# MCU.net
KiCad netlist of a schematic drawn in Altium Designer
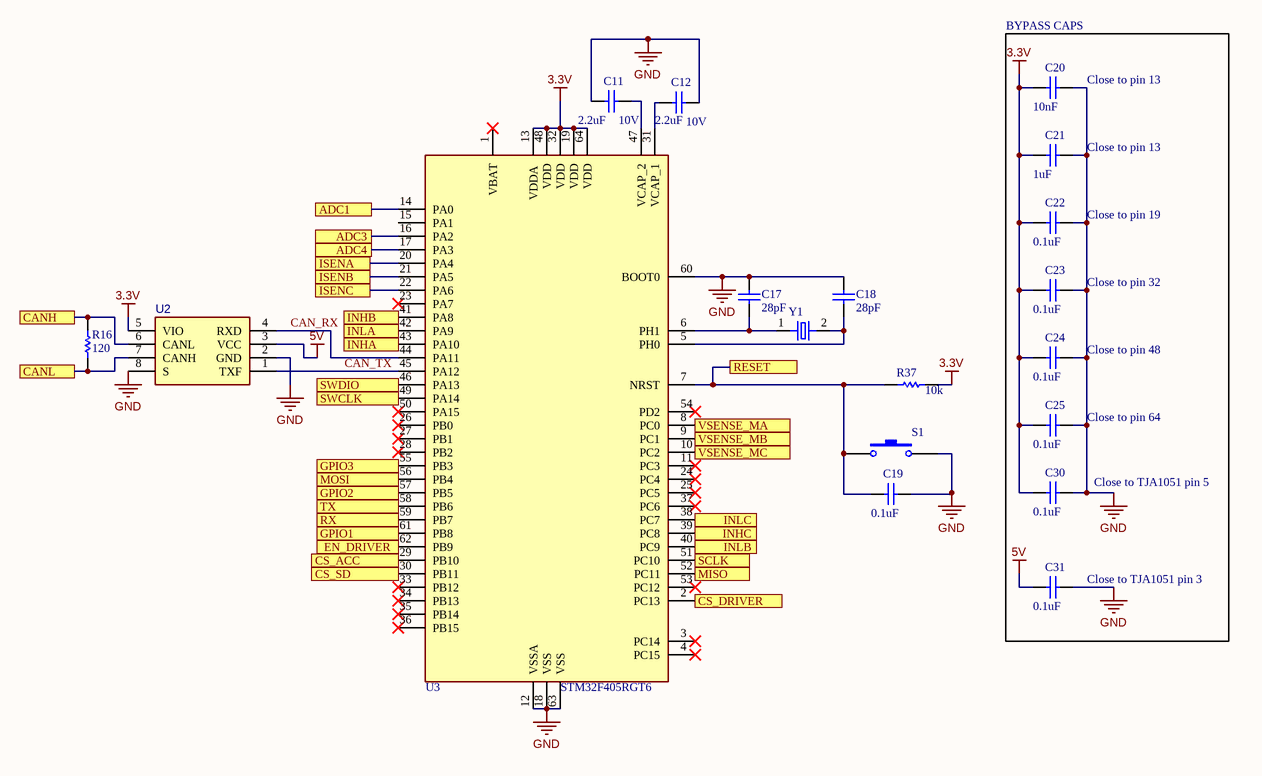
[diagram p0: MCU.SchDoc]

(export (version "E")
  (design (tool "Eeschema 10.0.6"))
  (components
    (comp (ref "C11")
      (value "10V")
      (footprint "0805 - Capacitor")
      (description "Nonpolarized Capacitor")
      (fields (field (name "ALTIUM_VALUE") "2.2uF"))
      (libsource (lib "General") (part "Capacitor - Nonpolarized"))
    )
    (comp (ref "C12")
      (value "10V")
      (footprint "0805 - Capacitor")
      (description "Nonpolarized Capacitor")
      (fields (field (name "ALTIUM_VALUE") "2.2uF"))
      (libsource (lib "General") (part "Capacitor - Nonpolarized"))
    )
    (comp (ref "C17")
      (value "28pF")
      (footprint "0805 - Capacitor")
      (description "CL21B104KCFNNNE, MULTILAYER CERAMIC CAPACITORS MLCC - SMD/SMT 100NF 100V 0805 ROHS")
      (fields (field (name "Comment") "100V"))
      (libsource (lib "General") (part "Capacitor - Nonpolarized"))
    )
    (comp (ref "C18")
      (value "28pF")
      (footprint "0805 - Capacitor")
      (description "CL21B104KCFNNNE, MULTILAYER CERAMIC CAPACITORS MLCC - SMD/SMT 100NF 100V 0805 ROHS")
      (fields (field (name "Comment") "100V"))
      (libsource (lib "General") (part "Capacitor - Nonpolarized"))
    )
    (comp (ref "C19")
      (value "0.1uF")
      (footprint "0805 - Capacitor")
      (description "CL21B104KCFNNNE, MULTILAYER CERAMIC CAPACITORS MLCC - SMD/SMT 100NF 100V 0805 ROHS")
      (fields (field (name "Comment") "100V"))
      (libsource (lib "General") (part "Capacitor - Nonpolarized"))
    )
    (comp (ref "C20")
      (value "10nF")
      (footprint "0805 - Capacitor")
      (description "C0805C103K8RAC7800. 10000pF ±10% 10V Ceramic Capacitor X7R 0805 (2012 Metric)")
      (fields (field (name "Comment") "10V"))
      (libsource (lib "General") (part "Capacitor - Nonpolarized"))
    )
    (comp (ref "C21")
      (value "1uF")
      (footprint "0805 - Capacitor")
      (description "TDK C2012X7S2A105KT000N, 1UF ±10% 100V X7S 0805 MULTILAYER CERAMIC CAPACITORS MLCC - SMD/SMT ROHS")
      (fields (field (name "Comment") "100V"))
      (libsource (lib "General") (part "Capacitor - Nonpolarized"))
    )
    (comp (ref "C22")
      (value "0.1uF")
      (footprint "0805 - Capacitor")
      (description "CL21B104KCFNNNE, MULTILAYER CERAMIC CAPACITORS MLCC - SMD/SMT 100NF 100V 0805 ROHS")
      (fields (field (name "Comment") "100V"))
      (libsource (lib "General") (part "Capacitor - Nonpolarized"))
    )
    (comp (ref "C23")
      (value "0.1uF")
      (footprint "0805 - Capacitor")
      (description "CL21B104KCFNNNE, MULTILAYER CERAMIC CAPACITORS MLCC - SMD/SMT 100NF 100V 0805 ROHS")
      (fields (field (name "Comment") "100V"))
      (libsource (lib "General") (part "Capacitor - Nonpolarized"))
    )
    (comp (ref "C24")
      (value "0.1uF")
      (footprint "0805 - Capacitor")
      (description "CL21B104KCFNNNE, MULTILAYER CERAMIC CAPACITORS MLCC - SMD/SMT 100NF 100V 0805 ROHS")
      (fields (field (name "Comment") "100V"))
      (libsource (lib "General") (part "Capacitor - Nonpolarized"))
    )
    (comp (ref "C25")
      (value "0.1uF")
      (footprint "0805 - Capacitor")
      (description "CL21B104KCFNNNE, MULTILAYER CERAMIC CAPACITORS MLCC - SMD/SMT 100NF 100V 0805 ROHS")
      (fields (field (name "Comment") "100V"))
      (libsource (lib "General") (part "Capacitor - Nonpolarized"))
    )
    (comp (ref "C30")
      (value "0.1uF")
      (footprint "0805 - Capacitor")
      (description "CL21B104KCFNNNE, MULTILAYER CERAMIC CAPACITORS MLCC - SMD/SMT 100NF 100V 0805 ROHS")
      (fields (field (name "Comment") "100V"))
      (libsource (lib "General") (part "Capacitor - Nonpolarized"))
    )
    (comp (ref "C31")
      (value "0.1uF")
      (footprint "0805 - Capacitor")
      (description "CL21B104KCFNNNE, MULTILAYER CERAMIC CAPACITORS MLCC - SMD/SMT 100NF 100V 0805 ROHS")
      (fields (field (name "Comment") "100V"))
      (libsource (lib "General") (part "Capacitor - Nonpolarized"))
    )
    (comp (ref "R16")
      (value "120")
      (footprint "0603 - Resistor")
      (description "Resistor")
      (fields (field (name "Comment") "500m"))
      (libsource (lib "General") (part "Resistor"))
    )
    (comp (ref "R37")
      (value "10k")
      (footprint "0603 - Resistor")
      (description "Resistor")
      (libsource (lib "General") (part "Resistor"))
    )
    (comp (ref "S1")
      (value "Switch - Push Button")
      (footprint "6x6mm Switch")
      (description "Push Button Switch")
      (libsource (lib "General") (part "Switch - Push Button"))
    )
    (comp (ref "U2")
      (value "~")
      (footprint "TJA1051T/3,118")
      (description "Integrated Circuit")
      (fields
        (field (name "MANUFACTURER_PART_NUMBER") "TJA1051T/3,118")
        (field (name "MOUSER PART NUMBER") "771-TJA1051T3118")
      )
      (libsource (lib "GeneralComponents") (part "TJA1051T_3,118"))
    )
    (comp (ref "U3")
      (value "STM32F405RGT6")
      (footprint "STM32F405RG")
      (description "ST 64-pin Micro")
      (fields (field (name "MANUFACTURER PART NUMBER") "STM32F405RG") (field (name "MANUFACTURER") "ST"))
      (libsource (lib "GeneralComponents") (part "STM32F405RGT6"))
    )
    (comp (ref "Y1")
      (value "ABM3-16.000MHZ-B2-T")
      (footprint "ABM3-16.000MHZ-B2-T")
      (description "16MHz Â±20ppm Crystal 18pF 40 Ohms 2-SMD, No Lead")
      (fields (field (name "DIGI-KEY_PART_NUMBER") "535-9103-1-ND") (field (name "MF") "Abracon"))
      (libsource (lib "MC") (part "ABM3-16.000MHZ-B2-T"))
    )
  )
  (nets
    (net (code "1") (name "/ADC1") (class "Default")
      (node (ref "U3") (pin "14") (pinfunction "PA0_14") (pintype "passive"))
    )
    (net (code "2") (name "/ADC3") (class "Default")
      (node (ref "U3") (pin "16") (pinfunction "PA2_16") (pintype "passive"))
    )
    (net (code "3") (name "/ADC4") (class "Default")
      (node (ref "U3") (pin "17") (pinfunction "PA3_17") (pintype "passive"))
    )
    (net (code "4") (name "/CANH") (class "Default")
      (node (ref "R16") (pin "1") (pinfunction "1_1") (pintype "passive"))
      (node (ref "U2") (pin "6") (pinfunction "CANL_6") (pintype "passive"))
    )
    (net (code "5") (name "/CANL") (class "Default")
      (node (ref "R16") (pin "2") (pinfunction "2_2") (pintype "passive"))
      (node (ref "U2") (pin "7") (pinfunction "CANH_7") (pintype "passive"))
    )
    (net (code "6") (name "/CAN_RX") (class "Default")
      (node (ref "U2") (pin "4") (pinfunction "RXD_4") (pintype "passive"))
      (node (ref "U3") (pin "44") (pinfunction "PA11_44") (pintype "passive"))
    )
    (net (code "7") (name "/CAN_TX") (class "Default")
      (node (ref "U2") (pin "1") (pinfunction "TXF_1") (pintype "passive"))
      (node (ref "U3") (pin "45") (pinfunction "PA12_45") (pintype "passive"))
    )
    (net (code "8") (name "/CS_ACC") (class "Default")
      (node (ref "U3") (pin "29") (pinfunction "PB10_29") (pintype "passive"))
    )
    (net (code "9") (name "/CS_DRIVER") (class "Default")
      (node (ref "U3") (pin "2") (pinfunction "PC13_2") (pintype "passive"))
    )
    (net (code "10") (name "/CS_SD") (class "Default")
      (node (ref "U3") (pin "30") (pinfunction "PB11_30") (pintype "passive"))
    )
    (net (code "11") (name "/EN_DRIVER") (class "Default")
      (node (ref "U3") (pin "62") (pinfunction "PB9_62") (pintype "passive"))
    )
    (net (code "12") (name "/GPIO1") (class "Default")
      (node (ref "U3") (pin "61") (pinfunction "PB8_61") (pintype "passive"))
    )
    (net (code "13") (name "/GPIO2") (class "Default")
      (node (ref "U3") (pin "57") (pinfunction "PB5_57") (pintype "passive"))
    )
    (net (code "14") (name "/GPIO3") (class "Default")
      (node (ref "U3") (pin "55") (pinfunction "PB3_55") (pintype "passive"))
    )
    (net (code "15") (name "/INHA") (class "Default")
      (node (ref "U3") (pin "43") (pinfunction "PA10_43") (pintype "passive"))
    )
    (net (code "16") (name "/INHB") (class "Default")
      (node (ref "U3") (pin "41") (pinfunction "PA8_41") (pintype "passive"))
    )
    (net (code "17") (name "/INHC") (class "Default")
      (node (ref "U3") (pin "39") (pinfunction "PC8_39") (pintype "passive"))
    )
    (net (code "18") (name "/INLA") (class "Default")
      (node (ref "U3") (pin "42") (pinfunction "PA9_42") (pintype "passive"))
    )
    (net (code "19") (name "/INLB") (class "Default")
      (node (ref "U3") (pin "40") (pinfunction "PC9_40") (pintype "passive"))
    )
    (net (code "20") (name "/INLC") (class "Default")
      (node (ref "U3") (pin "38") (pinfunction "PC7_38") (pintype "passive"))
    )
    (net (code "21") (name "/ISENA") (class "Default")
      (node (ref "U3") (pin "20") (pinfunction "PA4_20") (pintype "passive"))
    )
    (net (code "22") (name "/ISENB") (class "Default")
      (node (ref "U3") (pin "21") (pinfunction "PA5_21") (pintype "passive"))
    )
    (net (code "23") (name "/ISENC") (class "Default")
      (node (ref "U3") (pin "22") (pinfunction "PA6_22") (pintype "passive"))
    )
    (net (code "24") (name "/MISO") (class "Default")
      (node (ref "U3") (pin "52") (pinfunction "PC11_52") (pintype "passive"))
    )
    (net (code "25") (name "/MOSI") (class "Default")
      (node (ref "U3") (pin "56") (pinfunction "PB4_56") (pintype "passive"))
    )
    (net (code "26") (name "/RESET") (class "Default")
      (node (ref "C19") (pin "1") (pinfunction "1_1") (pintype "passive"))
      (node (ref "R37") (pin "2") (pinfunction "2_2") (pintype "passive"))
      (node (ref "S1") (pin "1") (pinfunction "1_1") (pintype "passive"))
      (node (ref "U3") (pin "7") (pinfunction "NRST_7") (pintype "passive"))
    )
    (net (code "27") (name "/RX") (class "Default")
      (node (ref "U3") (pin "59") (pinfunction "PB7_59") (pintype "passive"))
    )
    (net (code "28") (name "/SCLK") (class "Default")
      (node (ref "U3") (pin "51") (pinfunction "PC10_51") (pintype "passive"))
    )
    (net (code "29") (name "/SWCLK") (class "Default")
      (node (ref "U3") (pin "49") (pinfunction "PA14_49") (pintype "passive"))
    )
    (net (code "30") (name "/SWDIO") (class "Default")
      (node (ref "U3") (pin "46") (pinfunction "PA13_46") (pintype "passive"))
    )
    (net (code "31") (name "/TX") (class "Default")
      (node (ref "U3") (pin "58") (pinfunction "PB6_58") (pintype "passive"))
    )
    (net (code "32") (name "/VSENSE_MA") (class "Default")
      (node (ref "U3") (pin "8") (pinfunction "PC0_8") (pintype "passive"))
    )
    (net (code "33") (name "/VSENSE_MB") (class "Default")
      (node (ref "U3") (pin "9") (pinfunction "PC1_9") (pintype "passive"))
    )
    (net (code "34") (name "/VSENSE_MC") (class "Default")
      (node (ref "U3") (pin "10") (pinfunction "PC2_10") (pintype "passive"))
    )
    (net (code "35") (name "3.3V") (class "Default")
      (node (ref "C20") (pin "1") (pinfunction "1_1") (pintype "passive"))
      (node (ref "C21") (pin "1") (pinfunction "1_1") (pintype "passive"))
      (node (ref "C22") (pin "1") (pinfunction "1_1") (pintype "passive"))
      (node (ref "C23") (pin "1") (pinfunction "1_1") (pintype "passive"))
      (node (ref "C24") (pin "1") (pinfunction "1_1") (pintype "passive"))
      (node (ref "C25") (pin "1") (pinfunction "1_1") (pintype "passive"))
      (node (ref "C30") (pin "1") (pinfunction "1_1") (pintype "passive"))
      (node (ref "R37") (pin "1") (pinfunction "1_1") (pintype "passive"))
      (node (ref "U2") (pin "5") (pinfunction "VIO_5") (pintype "passive"))
      (node (ref "U3") (pin "13") (pinfunction "VDDA_13") (pintype "power_in"))
      (node (ref "U3") (pin "19") (pinfunction "VDD_19") (pintype "power_in"))
      (node (ref "U3") (pin "32") (pinfunction "VDD_32") (pintype "power_in"))
      (node (ref "U3") (pin "48") (pinfunction "VDD_48") (pintype "power_in"))
      (node (ref "U3") (pin "64") (pinfunction "VDD_64") (pintype "power_in"))
    )
    (net (code "36") (name "5V") (class "Default")
      (node (ref "C31") (pin "1") (pinfunction "1_1") (pintype "passive"))
      (node (ref "U2") (pin "3") (pinfunction "VCC_3") (pintype "passive"))
    )
    (net (code "37") (name "GND") (class "Default")
      (node (ref "C11") (pin "1") (pinfunction "1_1") (pintype "passive"))
      (node (ref "C12") (pin "2") (pinfunction "2_2") (pintype "passive"))
      (node (ref "C17") (pin "2") (pinfunction "2_2") (pintype "passive"))
      (node (ref "C18") (pin "2") (pinfunction "2_2") (pintype "passive"))
      (node (ref "C19") (pin "2") (pinfunction "2_2") (pintype "passive"))
      (node (ref "C20") (pin "2") (pinfunction "2_2") (pintype "passive"))
      (node (ref "C21") (pin "2") (pinfunction "2_2") (pintype "passive"))
      (node (ref "C22") (pin "2") (pinfunction "2_2") (pintype "passive"))
      (node (ref "C23") (pin "2") (pinfunction "2_2") (pintype "passive"))
      (node (ref "C24") (pin "2") (pinfunction "2_2") (pintype "passive"))
      (node (ref "C25") (pin "2") (pinfunction "2_2") (pintype "passive"))
      (node (ref "C30") (pin "2") (pinfunction "2_2") (pintype "passive"))
      (node (ref "C31") (pin "2") (pinfunction "2_2") (pintype "passive"))
      (node (ref "S1") (pin "2") (pinfunction "2_2") (pintype "passive"))
      (node (ref "U2") (pin "2") (pinfunction "GND_2") (pintype "passive"))
      (node (ref "U2") (pin "8") (pinfunction "S_8") (pintype "passive"))
      (node (ref "U3") (pin "12") (pinfunction "VSSA_12") (pintype "power_in"))
      (node (ref "U3") (pin "18") (pinfunction "VSS_18") (pintype "power_in"))
      (node (ref "U3") (pin "60") (pinfunction "BOOT0_60") (pintype "passive"))
      (node (ref "U3") (pin "63") (pinfunction "VSS_63") (pintype "power_in"))
    )
    (net (code "38") (name "Net-(U3-PH0)") (class "Default")
      (node (ref "C18") (pin "1") (pinfunction "1_1") (pintype "passive"))
      (node (ref "U3") (pin "5") (pinfunction "PH0_5") (pintype "passive"))
      (node (ref "Y1") (pin "2") (pinfunction "2_2") (pintype "passive"))
    )
    (net (code "39") (name "Net-(U3-PH1)") (class "Default")
      (node (ref "C17") (pin "1") (pinfunction "1_1") (pintype "passive"))
      (node (ref "U3") (pin "6") (pinfunction "PH1_6") (pintype "passive"))
      (node (ref "Y1") (pin "1") (pinfunction "1_1") (pintype "passive"))
    )
    (net (code "40") (name "Net-(U3-VCAP_1)") (class "Default")
      (node (ref "C12") (pin "1") (pinfunction "1_1") (pintype "passive"))
      (node (ref "U3") (pin "31") (pinfunction "VCAP_1_31") (pintype "power_in"))
    )
    (net (code "41") (name "Net-(U3-VCAP_2)") (class "Default")
      (node (ref "C11") (pin "2") (pinfunction "2_2") (pintype "passive"))
      (node (ref "U3") (pin "47") (pinfunction "VCAP_2_47") (pintype "power_in"))
    )
    (net (code "42") (name "unconnected-(U3-PA1-Pad15)") (class "Default")
      (node (ref "U3") (pin "15") (pinfunction "PA1_15") (pintype "passive"))
    )
    (net (code "43") (name "unconnected-(U3-PA7-Pad23)") (class "Default")
      (node (ref "U3") (pin "23") (pinfunction "PA7_23") (pintype "passive+no_connect"))
    )
    (net (code "44") (name "unconnected-(U3-PA15-Pad50)") (class "Default")
      (node (ref "U3") (pin "50") (pinfunction "PA15_50") (pintype "passive+no_connect"))
    )
    (net (code "45") (name "unconnected-(U3-PB0-Pad26)") (class "Default")
      (node (ref "U3") (pin "26") (pinfunction "PB0_26") (pintype "passive+no_connect"))
    )
    (net (code "46") (name "unconnected-(U3-PB1-Pad27)") (class "Default")
      (node (ref "U3") (pin "27") (pinfunction "PB1_27") (pintype "passive+no_connect"))
    )
    (net (code "47") (name "unconnected-(U3-PB2-Pad28)") (class "Default")
      (node (ref "U3") (pin "28") (pinfunction "PB2_28") (pintype "passive+no_connect"))
    )
    (net (code "48") (name "unconnected-(U3-PB12-Pad33)") (class "Default")
      (node (ref "U3") (pin "33") (pinfunction "PB12_33") (pintype "passive+no_connect"))
    )
    (net (code "49") (name "unconnected-(U3-PB13-Pad34)") (class "Default")
      (node (ref "U3") (pin "34") (pinfunction "PB13_34") (pintype "passive+no_connect"))
    )
    (net (code "50") (name "unconnected-(U3-PB14-Pad35)") (class "Default")
      (node (ref "U3") (pin "35") (pinfunction "PB14_35") (pintype "passive+no_connect"))
    )
    (net (code "51") (name "unconnected-(U3-PB15-Pad36)") (class "Default")
      (node (ref "U3") (pin "36") (pinfunction "PB15_36") (pintype "passive+no_connect"))
    )
    (net (code "52") (name "unconnected-(U3-PC3-Pad11)") (class "Default")
      (node (ref "U3") (pin "11") (pinfunction "PC3_11") (pintype "passive+no_connect"))
    )
    (net (code "53") (name "unconnected-(U3-PC4-Pad24)") (class "Default")
      (node (ref "U3") (pin "24") (pinfunction "PC4_24") (pintype "passive+no_connect"))
    )
    (net (code "54") (name "unconnected-(U3-PC5-Pad25)") (class "Default")
      (node (ref "U3") (pin "25") (pinfunction "PC5_25") (pintype "passive+no_connect"))
    )
    (net (code "55") (name "unconnected-(U3-PC6-Pad37)") (class "Default")
      (node (ref "U3") (pin "37") (pinfunction "PC6_37") (pintype "passive+no_connect"))
    )
    (net (code "56") (name "unconnected-(U3-PC12-Pad53)") (class "Default")
      (node (ref "U3") (pin "53") (pinfunction "PC12_53") (pintype "passive+no_connect"))
    )
    (net (code "57") (name "unconnected-(U3-PC14-Pad3)") (class "Default")
      (node (ref "U3") (pin "3") (pinfunction "PC14_3") (pintype "passive+no_connect"))
    )
    (net (code "58") (name "unconnected-(U3-PC15-Pad4)") (class "Default")
      (node (ref "U3") (pin "4") (pinfunction "PC15_4") (pintype "passive+no_connect"))
    )
    (net (code "59") (name "unconnected-(U3-PD2-Pad54)") (class "Default")
      (node (ref "U3") (pin "54") (pinfunction "PD2_54") (pintype "passive+no_connect"))
    )
    (net (code "60") (name "unconnected-(U3-VBAT-Pad1)") (class "Default")
      (node (ref "U3") (pin "1") (pinfunction "VBAT_1") (pintype "power_in+no_connect"))
    )
  )
)
